# 05_MIMXRT1170_PART1.net
KiCad netlist of a schematic drawn in Altium Designer
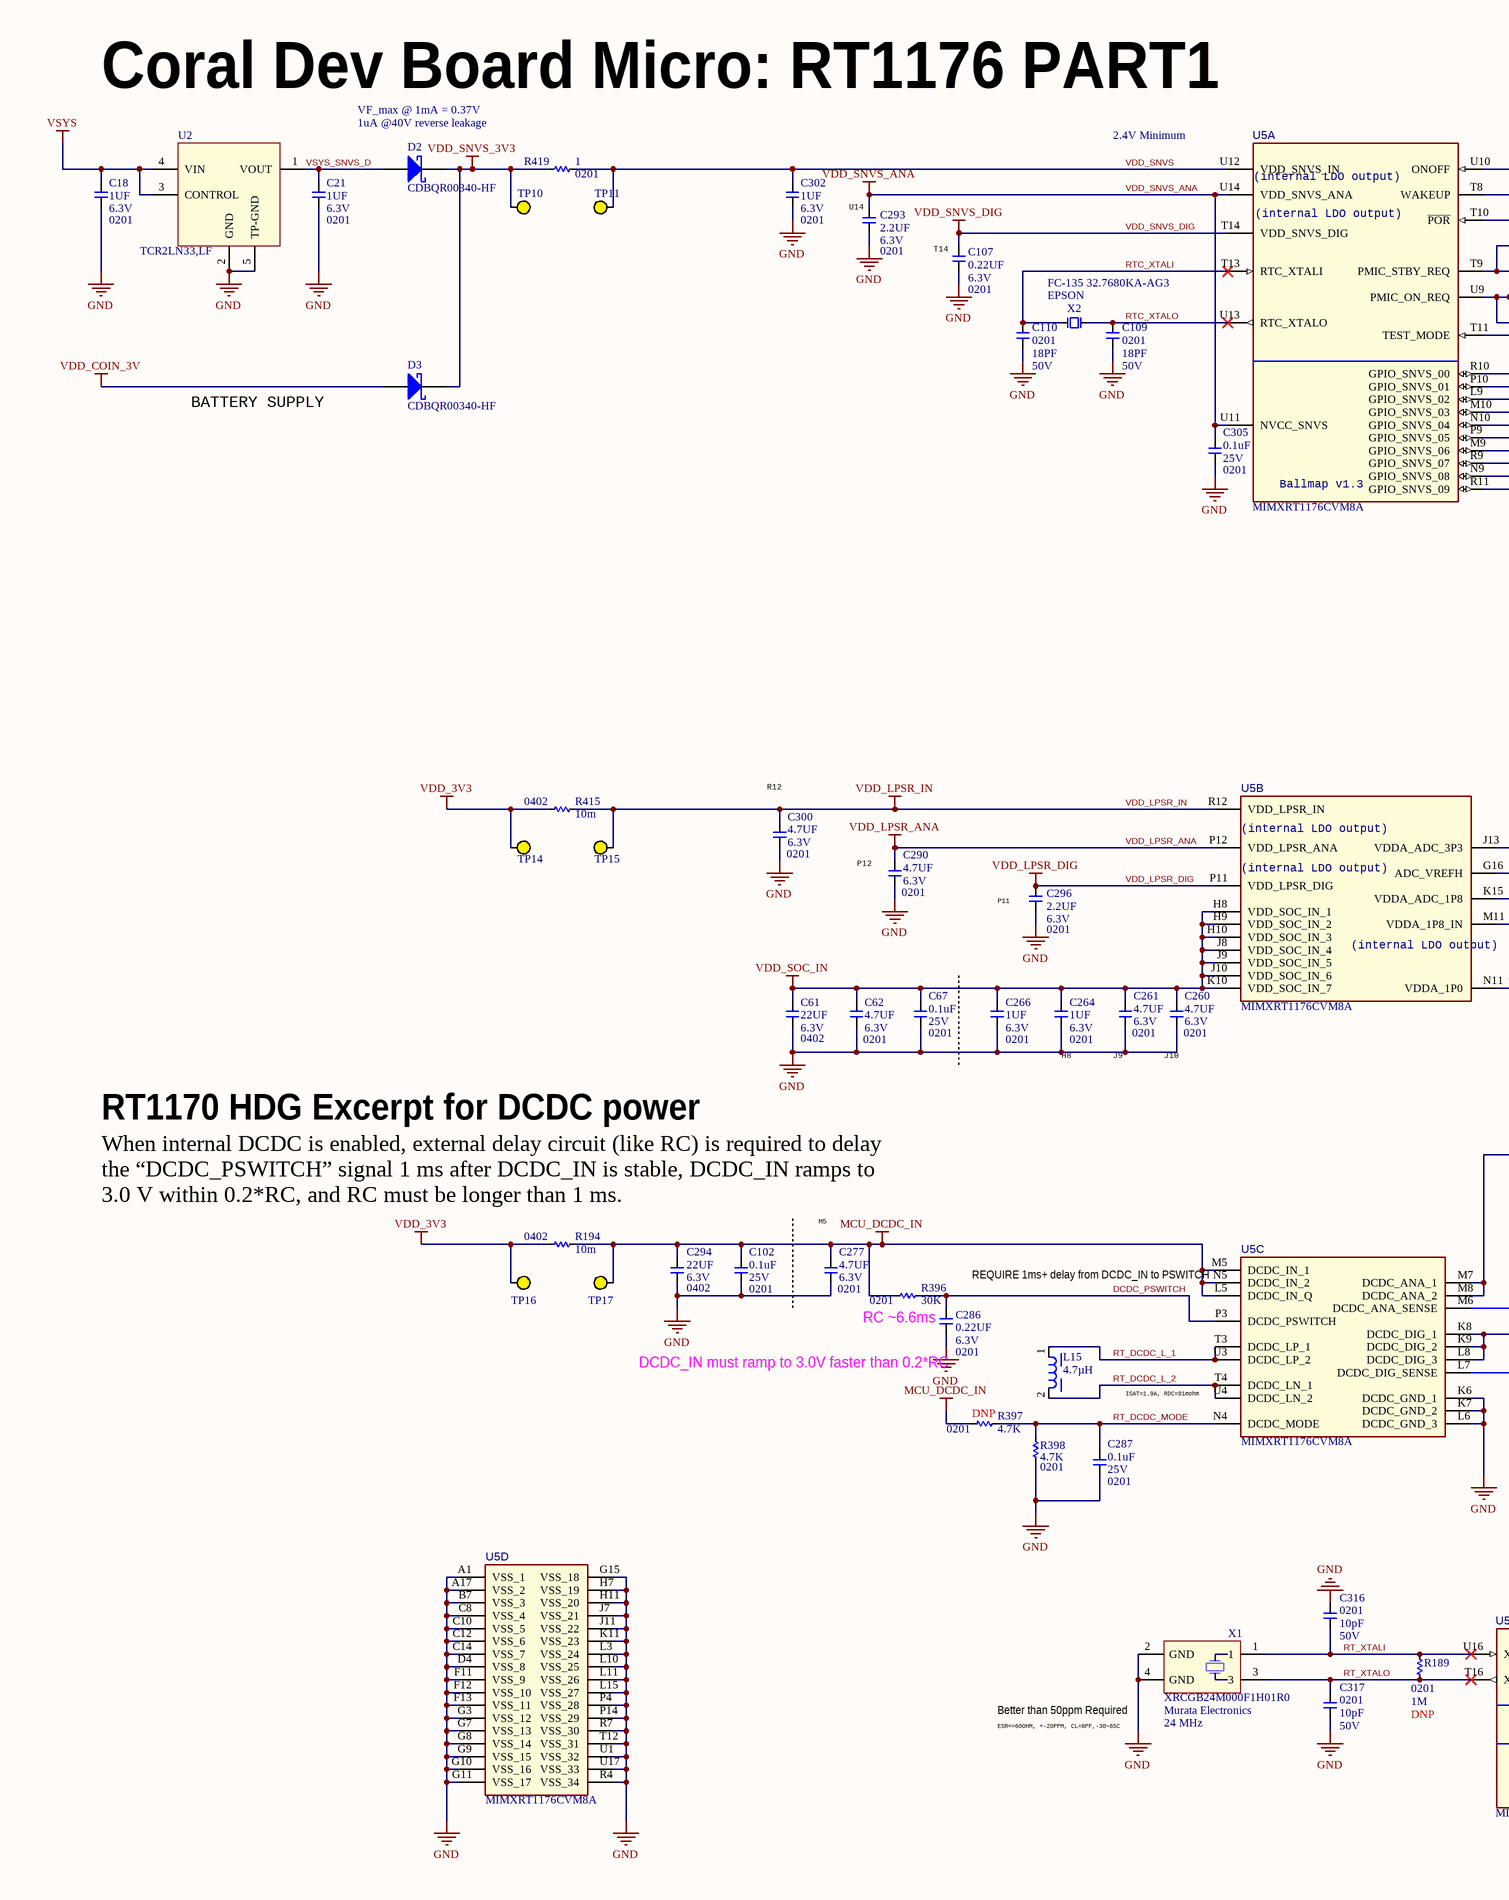
[diagram p0: 05 MIMXRT1170 PART1.SchDoc, left]
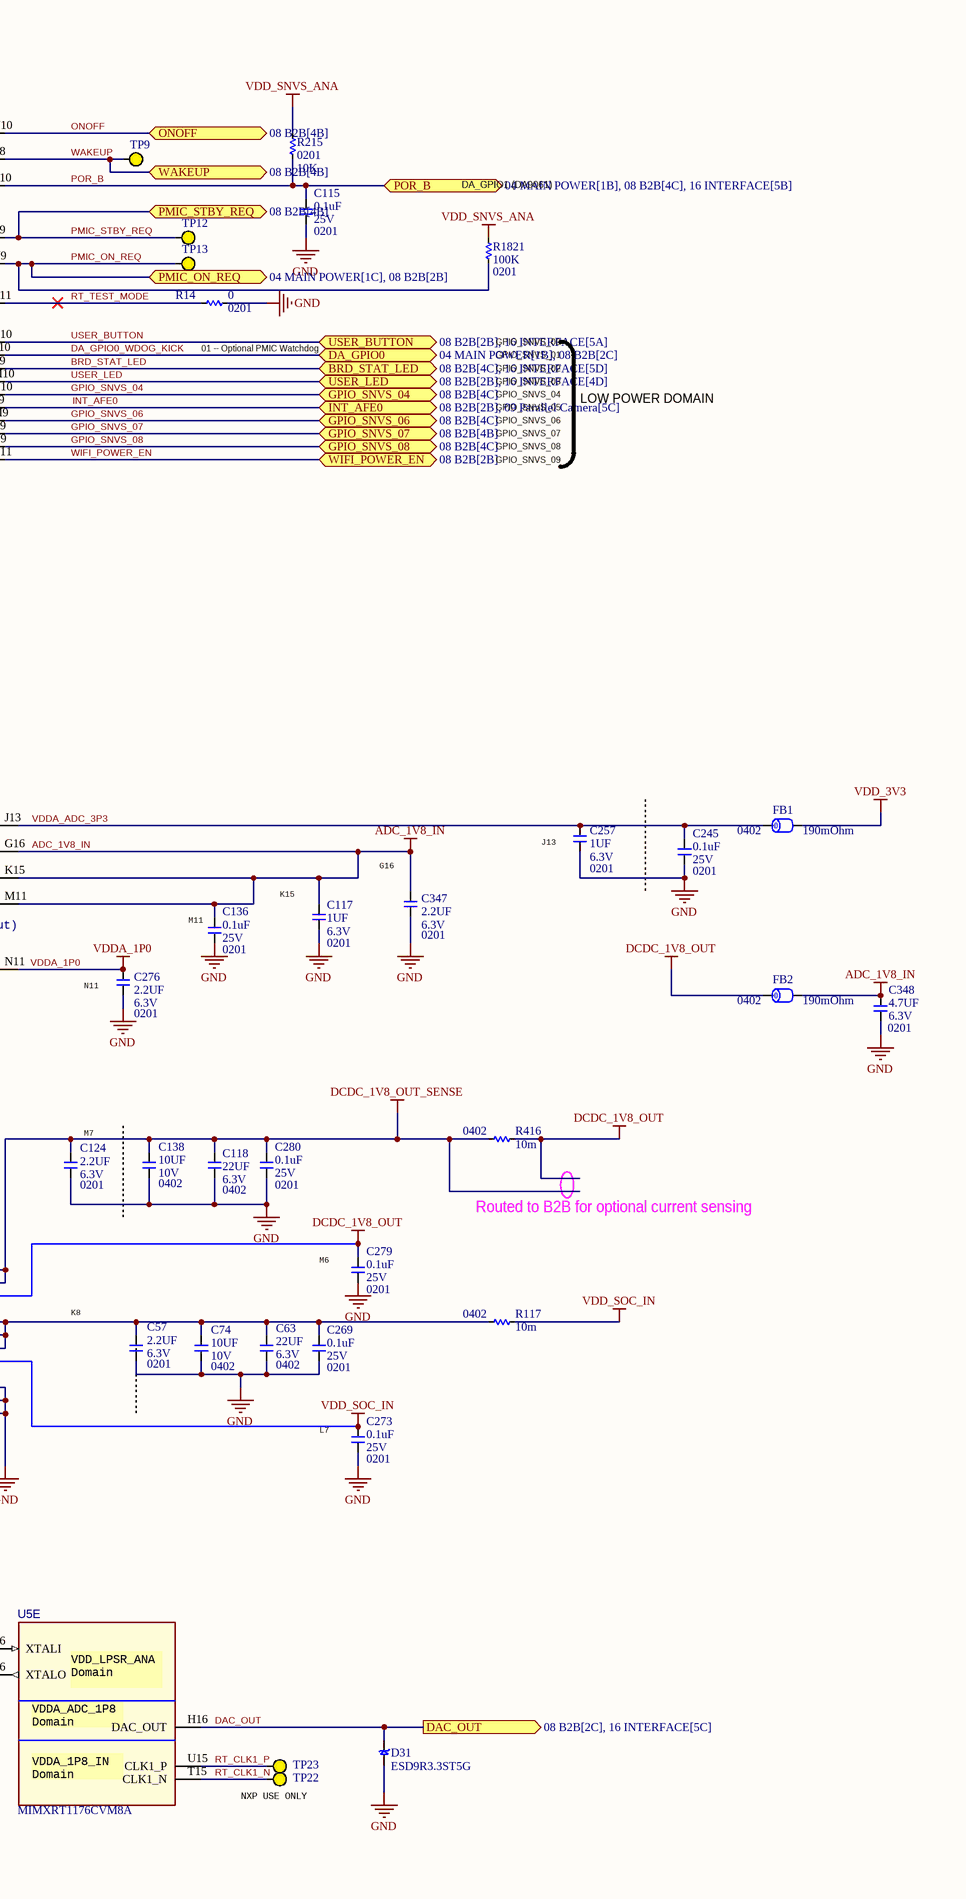
[diagram p1: 05 MIMXRT1170 PART1.SchDoc, right]

(export (version "E")
  (design (tool "Eeschema 10.0.6"))
  (components
    (comp (ref "C18")
      (value "1UF")
      (footprint "C0201_H0.39MM")
      (description "CAP, CER, X6S, 1uF, 20%, 6.3V, 0201, 0.39mm")
      (fields
        (field (name "MFG") "MURATA")
        (field (name "PACKAGE") "0201")
        (field (name "VOLTAGE") "6.3V")
        (field (name "TOLERANCE") "20%")
      )
      (libsource (lib "AltiumReleaseLibDB") (part "__Template_Cap"))
    )
    (comp (ref "C21")
      (value "1UF")
      (footprint "C0201_H0.39MM")
      (description "CAP, CER, X6S, 1uF, 20%, 6.3V, 0201, 0.39mm")
      (fields
        (field (name "MFG") "MURATA")
        (field (name "PACKAGE") "0201")
        (field (name "VOLTAGE") "6.3V")
        (field (name "TOLERANCE") "20%")
      )
      (libsource (lib "AltiumReleaseLibDB") (part "__Template_Cap"))
    )
    (comp (ref "C57")
      (value "2.2UF")
      (footprint "C0201_H0.39MM")
      (description "CAP, CER, X5R, 2.2uF, 20%, 6.3V, 0201, 0.39mm")
      (fields
        (field (name "MFG") "YAGEO")
        (field (name "PACKAGE") "0201")
        (field (name "VOLTAGE") "6.3V")
        (field (name "TOLERANCE") "20%")
      )
      (libsource (lib "AltiumReleaseLibDB") (part "__Template_Cap"))
    )
    (comp (ref "C61")
      (value "22UF")
      (footprint "C0402")
      (description "CAP, CER, X5R, 22uF, 20%, 6.3V, 0402")
      (fields
        (field (name "MFG") "AVX")
        (field (name "PACKAGE") "0402")
        (field (name "VOLTAGE") "6.3V")
        (field (name "TOLERANCE") "20%")
      )
      (libsource (lib "AltiumReleaseLibDB") (part "__Template_Cap"))
    )
    (comp (ref "C62")
      (value "4.7UF")
      (footprint "C0201Y")
      (description "CAP, CER, X5R, 4.7uF, 20%, 6.3V, 0201")
      (fields
        (field (name "MFG") "MURATA")
        (field (name "PACKAGE") "0201")
        (field (name "VOLTAGE") "6.3V")
        (field (name "TOLERANCE") "20%")
      )
      (libsource (lib "AltiumReleaseLibDB") (part "__Template_Cap"))
    )
    (comp (ref "C63")
      (value "22UF")
      (footprint "C0402")
      (description "CAP, CER, X5R, 22uF, 20%, 6.3V, 0402")
      (fields
        (field (name "MFG") "AVX")
        (field (name "PACKAGE") "0402")
        (field (name "VOLTAGE") "6.3V")
        (field (name "TOLERANCE") "20%")
      )
      (libsource (lib "AltiumReleaseLibDB") (part "__Template_Cap"))
    )
    (comp (ref "C67")
      (value "0.1uF")
      (footprint "C0201Y")
      (description "CAP, CER, X5R, 0.1uF, 25V, 20%, 0201, 0.33mm T")
      (fields
        (field (name "MFG") "MURATA")
        (field (name "PACKAGE") "0201")
        (field (name "VOLTAGE") "25V")
        (field (name "TOLERANCE") "20%")
      )
      (libsource (lib "AltiumReleaseLibDB") (part "__Template_Cap"))
    )
    (comp (ref "C74")
      (value "10UF")
      (footprint "C0402")
      (description "CAP, CER, X5R, 10uF, 10V, 20%, 0402, 0.7mm T")
      (fields
        (field (name "MFG") "SAMSUNG")
        (field (name "PACKAGE") "0402")
        (field (name "VOLTAGE") "10V")
        (field (name "TOLERANCE") "20%")
      )
      (libsource (lib "AltiumReleaseLibDB") (part "__Template_Cap"))
    )
    (comp (ref "C102")
      (value "0.1uF")
      (footprint "C0201Y")
      (description "CAP, CER, X5R, 0.1uF, 25V, 20%, 0201, 0.33mm T")
      (fields
        (field (name "MFG") "MURATA")
        (field (name "PACKAGE") "0201")
        (field (name "VOLTAGE") "25V")
        (field (name "TOLERANCE") "20%")
      )
      (libsource (lib "AltiumReleaseLibDB") (part "__Template_Cap"))
    )
    (comp (ref "C107")
      (value "0.22UF")
      (footprint "C0201")
      (description "CAP, CER, X5R, 0.22uF, 6.3V, 10%, 0201, 0.33mm T")
      (fields
        (field (name "MFG") "TDK")
        (field (name "PACKAGE") "0201")
        (field (name "VOLTAGE") "6.3V")
        (field (name "TOLERANCE") "10%")
      )
      (libsource (lib "AltiumReleaseLibDB") (part "__Template_Cap"))
    )
    (comp (ref "C109")
      (value "18PF")
      (footprint "C0201Y")
      (description "CAP, CER, C0G, 18pF, 50V, 2%, 0201, 0.33mm T")
      (fields
        (field (name "MFG") "MURATA")
        (field (name "PACKAGE") "0201")
        (field (name "VOLTAGE") "50V")
        (field (name "TOLERANCE") "2%")
      )
      (libsource (lib "AltiumReleaseLibDB") (part "__Template_Cap"))
    )
    (comp (ref "C110")
      (value "18PF")
      (footprint "C0201Y")
      (description "CAP, CER, C0G, 18pF, 50V, 2%, 0201, 0.33mm T")
      (fields
        (field (name "MFG") "MURATA")
        (field (name "PACKAGE") "0201")
        (field (name "VOLTAGE") "50V")
        (field (name "TOLERANCE") "2%")
      )
      (libsource (lib "AltiumReleaseLibDB") (part "__Template_Cap"))
    )
    (comp (ref "C115")
      (value "0.1uF")
      (footprint "C0201Y")
      (description "CAP, CER, X5R, 0.1uF, 25V, 20%, 0201, 0.33mm T")
      (fields
        (field (name "MFG") "MURATA")
        (field (name "PACKAGE") "0201")
        (field (name "VOLTAGE") "25V")
        (field (name "TOLERANCE") "20%")
      )
      (libsource (lib "AltiumReleaseLibDB") (part "__Template_Cap"))
    )
    (comp (ref "C117")
      (value "1UF")
      (footprint "C0201_H0.39MM")
      (description "CAP, CER, X6S, 1uF, 20%, 6.3V, 0201, 0.39mm")
      (fields
        (field (name "MFG") "MURATA")
        (field (name "PACKAGE") "0201")
        (field (name "VOLTAGE") "6.3V")
        (field (name "TOLERANCE") "20%")
      )
      (libsource (lib "AltiumReleaseLibDB") (part "__Template_Cap"))
    )
    (comp (ref "C118")
      (value "22UF")
      (footprint "C0402")
      (description "CAP, CER, X5R, 22uF, 20%, 6.3V, 0402")
      (fields
        (field (name "MFG") "AVX")
        (field (name "PACKAGE") "0402")
        (field (name "VOLTAGE") "6.3V")
        (field (name "TOLERANCE") "20%")
      )
      (libsource (lib "AltiumReleaseLibDB") (part "__Template_Cap"))
    )
    (comp (ref "C124")
      (value "2.2UF")
      (footprint "C0201_H0.39MM")
      (description "CAP, CER, X5R, 2.2uF, 20%, 6.3V, 0201, 0.39mm")
      (fields
        (field (name "MFG") "YAGEO")
        (field (name "PACKAGE") "0201")
        (field (name "VOLTAGE") "6.3V")
        (field (name "TOLERANCE") "20%")
      )
      (libsource (lib "AltiumReleaseLibDB") (part "__Template_Cap"))
    )
    (comp (ref "C136")
      (value "0.1uF")
      (footprint "C0201Y")
      (description "CAP, CER, X5R, 0.1uF, 25V, 20%, 0201, 0.33mm T")
      (fields
        (field (name "MFG") "MURATA")
        (field (name "PACKAGE") "0201")
        (field (name "VOLTAGE") "25V")
        (field (name "TOLERANCE") "20%")
      )
      (libsource (lib "AltiumReleaseLibDB") (part "__Template_Cap"))
    )
    (comp (ref "C138")
      (value "10UF")
      (footprint "C0402")
      (description "CAP, CER, X5R, 10uF, 10V, 20%, 0402, 0.7mm T")
      (fields
        (field (name "MFG") "SAMSUNG")
        (field (name "PACKAGE") "0402")
        (field (name "VOLTAGE") "10V")
        (field (name "TOLERANCE") "20%")
      )
      (libsource (lib "AltiumReleaseLibDB") (part "__Template_Cap"))
    )
    (comp (ref "C245")
      (value "0.1uF")
      (footprint "C0201Y")
      (description "CAP, CER, X5R, 0.1uF, 25V, 20%, 0201, 0.33mm T")
      (fields
        (field (name "MFG") "MURATA")
        (field (name "PACKAGE") "0201")
        (field (name "VOLTAGE") "25V")
        (field (name "TOLERANCE") "20%")
      )
      (libsource (lib "AltiumReleaseLibDB") (part "__Template_Cap"))
    )
    (comp (ref "C257")
      (value "1UF")
      (footprint "C0201_H0.39MM")
      (description "CAP, CER, X6S, 1uF, 20%, 6.3V, 0201, 0.39mm")
      (fields
        (field (name "MFG") "MURATA")
        (field (name "PACKAGE") "0201")
        (field (name "VOLTAGE") "6.3V")
        (field (name "TOLERANCE") "20%")
      )
      (libsource (lib "AltiumReleaseLibDB") (part "__Template_Cap"))
    )
    (comp (ref "C260")
      (value "4.7UF")
      (footprint "C0201Y")
      (description "CAP, CER, X5R, 4.7uF, 20%, 6.3V, 0201")
      (fields
        (field (name "MFG") "MURATA")
        (field (name "PACKAGE") "0201")
        (field (name "VOLTAGE") "6.3V")
        (field (name "TOLERANCE") "20%")
      )
      (libsource (lib "AltiumReleaseLibDB") (part "__Template_Cap"))
    )
    (comp (ref "C261")
      (value "4.7UF")
      (footprint "C0201Y")
      (description "CAP, CER, X5R, 4.7uF, 20%, 6.3V, 0201")
      (fields
        (field (name "MFG") "MURATA")
        (field (name "PACKAGE") "0201")
        (field (name "VOLTAGE") "6.3V")
        (field (name "TOLERANCE") "20%")
      )
      (libsource (lib "AltiumReleaseLibDB") (part "__Template_Cap"))
    )
    (comp (ref "C264")
      (value "1UF")
      (footprint "C0201_H0.39MM")
      (description "CAP, CER, X6S, 1uF, 20%, 6.3V, 0201, 0.39mm")
      (fields
        (field (name "MFG") "MURATA")
        (field (name "PACKAGE") "0201")
        (field (name "VOLTAGE") "6.3V")
        (field (name "TOLERANCE") "20%")
      )
      (libsource (lib "AltiumReleaseLibDB") (part "__Template_Cap"))
    )
    (comp (ref "C266")
      (value "1UF")
      (footprint "C0201_H0.39MM")
      (description "CAP, CER, X6S, 1uF, 20%, 6.3V, 0201, 0.39mm")
      (fields
        (field (name "MFG") "MURATA")
        (field (name "PACKAGE") "0201")
        (field (name "VOLTAGE") "6.3V")
        (field (name "TOLERANCE") "20%")
      )
      (libsource (lib "AltiumReleaseLibDB") (part "__Template_Cap"))
    )
    (comp (ref "C269")
      (value "0.1uF")
      (footprint "C0201Y")
      (description "CAP, CER, X5R, 0.1uF, 25V, 20%, 0201, 0.33mm T")
      (fields
        (field (name "MFG") "MURATA")
        (field (name "PACKAGE") "0201")
        (field (name "VOLTAGE") "25V")
        (field (name "TOLERANCE") "20%")
      )
      (libsource (lib "AltiumReleaseLibDB") (part "__Template_Cap"))
    )
    (comp (ref "C273")
      (value "0.1uF")
      (footprint "C0201Y")
      (description "CAP, CER, X5R, 0.1uF, 25V, 20%, 0201, 0.33mm T")
      (fields
        (field (name "MFG") "MURATA")
        (field (name "PACKAGE") "0201")
        (field (name "VOLTAGE") "25V")
        (field (name "TOLERANCE") "20%")
      )
      (libsource (lib "AltiumReleaseLibDB") (part "__Template_Cap"))
    )
    (comp (ref "C276")
      (value "2.2UF")
      (footprint "C0201_H0.39MM")
      (description "CAP, CER, X5R, 2.2uF, 20%, 6.3V, 0201, 0.39mm")
      (fields
        (field (name "MFG") "YAGEO")
        (field (name "PACKAGE") "0201")
        (field (name "VOLTAGE") "6.3V")
        (field (name "TOLERANCE") "20%")
      )
      (libsource (lib "AltiumReleaseLibDB") (part "__Template_Cap"))
    )
    (comp (ref "C277")
      (value "4.7UF")
      (footprint "C0201Y")
      (description "CAP, CER, X5R, 4.7uF, 20%, 6.3V, 0201")
      (fields
        (field (name "MFG") "MURATA")
        (field (name "PACKAGE") "0201")
        (field (name "VOLTAGE") "6.3V")
        (field (name "TOLERANCE") "20%")
      )
      (libsource (lib "AltiumReleaseLibDB") (part "__Template_Cap"))
    )
    (comp (ref "C279")
      (value "0.1uF")
      (footprint "C0201Y")
      (description "CAP, CER, X5R, 0.1uF, 25V, 20%, 0201, 0.33mm T")
      (fields
        (field (name "MFG") "MURATA")
        (field (name "PACKAGE") "0201")
        (field (name "VOLTAGE") "25V")
        (field (name "TOLERANCE") "20%")
      )
      (libsource (lib "AltiumReleaseLibDB") (part "__Template_Cap"))
    )
    (comp (ref "C280")
      (value "0.1uF")
      (footprint "C0201Y")
      (description "CAP, CER, X5R, 0.1uF, 25V, 20%, 0201, 0.33mm T")
      (fields
        (field (name "MFG") "MURATA")
        (field (name "PACKAGE") "0201")
        (field (name "VOLTAGE") "25V")
        (field (name "TOLERANCE") "20%")
      )
      (libsource (lib "AltiumReleaseLibDB") (part "__Template_Cap"))
    )
    (comp (ref "C286")
      (value "0.22UF")
      (footprint "C0201")
      (description "CAP, CER, X5R, 0.22uF, 6.3V, 10%, 0201, 0.33mm T")
      (fields
        (field (name "MFG") "TDK")
        (field (name "PACKAGE") "0201")
        (field (name "VOLTAGE") "6.3V")
        (field (name "TOLERANCE") "10%")
      )
      (libsource (lib "AltiumReleaseLibDB") (part "__Template_Cap"))
    )
    (comp (ref "C287")
      (value "0.1uF")
      (footprint "C0201Y")
      (description "CAP, CER, X5R, 0.1uF, 25V, 20%, 0201, 0.33mm T")
      (fields
        (field (name "MFG") "MURATA")
        (field (name "PACKAGE") "0201")
        (field (name "VOLTAGE") "25V")
        (field (name "TOLERANCE") "20%")
      )
      (libsource (lib "AltiumReleaseLibDB") (part "__Template_Cap"))
    )
    (comp (ref "C290")
      (value "4.7UF")
      (footprint "C0201Y")
      (description "CAP, CER, X5R, 4.7uF, 20%, 6.3V, 0201")
      (fields
        (field (name "MFG") "MURATA")
        (field (name "PACKAGE") "0201")
        (field (name "VOLTAGE") "6.3V")
        (field (name "TOLERANCE") "20%")
      )
      (libsource (lib "AltiumReleaseLibDB") (part "__Template_Cap"))
    )
    (comp (ref "C293")
      (value "2.2UF")
      (footprint "C0201_H0.39MM")
      (description "CAP, CER, X5R, 2.2uF, 20%, 6.3V, 0201, 0.39mm")
      (fields
        (field (name "MFG") "YAGEO")
        (field (name "PACKAGE") "0201")
        (field (name "VOLTAGE") "6.3V")
        (field (name "TOLERANCE") "20%")
      )
      (libsource (lib "AltiumReleaseLibDB") (part "__Template_Cap"))
    )
    (comp (ref "C294")
      (value "22UF")
      (footprint "C0402")
      (description "CAP, CER, X5R, 22uF, 20%, 6.3V, 0402")
      (fields
        (field (name "MFG") "AVX")
        (field (name "PACKAGE") "0402")
        (field (name "VOLTAGE") "6.3V")
        (field (name "TOLERANCE") "20%")
      )
      (libsource (lib "AltiumReleaseLibDB") (part "__Template_Cap"))
    )
    (comp (ref "C296")
      (value "2.2UF")
      (footprint "C0201_H0.39MM")
      (description "CAP, CER, X5R, 2.2uF, 20%, 6.3V, 0201, 0.39mm")
      (fields
        (field (name "MFG") "YAGEO")
        (field (name "PACKAGE") "0201")
        (field (name "VOLTAGE") "6.3V")
        (field (name "TOLERANCE") "20%")
      )
      (libsource (lib "AltiumReleaseLibDB") (part "__Template_Cap"))
    )
    (comp (ref "C300")
      (value "4.7UF")
      (footprint "C0201Y")
      (description "CAP, CER, X5R, 4.7uF, 20%, 6.3V, 0201")
      (fields
        (field (name "MFG") "MURATA")
        (field (name "PACKAGE") "0201")
        (field (name "VOLTAGE") "6.3V")
        (field (name "TOLERANCE") "20%")
      )
      (libsource (lib "AltiumReleaseLibDB") (part "__Template_Cap"))
    )
    (comp (ref "C302")
      (value "1UF")
      (footprint "C0201_H0.39MM")
      (description "CAP, CER, X6S, 1uF, 20%, 6.3V, 0201, 0.39mm")
      (fields
        (field (name "MFG") "MURATA")
        (field (name "PACKAGE") "0201")
        (field (name "VOLTAGE") "6.3V")
        (field (name "TOLERANCE") "20%")
      )
      (libsource (lib "AltiumReleaseLibDB") (part "__Template_Cap"))
    )
    (comp (ref "C305")
      (value "0.1uF")
      (footprint "C0201Y")
      (description "CAP, CER, X5R, 0.1uF, 25V, 20%, 0201, 0.33mm T")
      (fields
        (field (name "MFG") "MURATA")
        (field (name "PACKAGE") "0201")
        (field (name "VOLTAGE") "25V")
        (field (name "TOLERANCE") "20%")
      )
      (libsource (lib "AltiumReleaseLibDB") (part "__Template_Cap"))
    )
    (comp (ref "C316")
      (value "10pF")
      (footprint "C0201Y")
      (description "CAP, CER, NP0, 10pf, 50V, 5%, 0201, 0.33mm T")
      (fields
        (field (name "MFG") "MURATA")
        (field (name "PACKAGE") "0201")
        (field (name "VOLTAGE") "50V")
        (field (name "TOLERANCE") "5%")
      )
      (libsource (lib "AltiumReleaseLibDB") (part "__Template_Cap"))
    )
    (comp (ref "C317")
      (value "10pF")
      (footprint "C0201Y")
      (description "CAP, CER, NP0, 10pf, 50V, 5%, 0201, 0.33mm T")
      (fields
        (field (name "MFG") "MURATA")
        (field (name "PACKAGE") "0201")
        (field (name "VOLTAGE") "50V")
        (field (name "TOLERANCE") "5%")
      )
      (libsource (lib "AltiumReleaseLibDB") (part "__Template_Cap"))
    )
    (comp (ref "C347")
      (value "2.2UF")
      (footprint "C0201_H0.39MM")
      (description "CAP, CER, X5R, 2.2uF, 20%, 6.3V, 0201, 0.39mm")
      (fields
        (field (name "MFG") "YAGEO")
        (field (name "PACKAGE") "0201")
        (field (name "VOLTAGE") "6.3V")
        (field (name "TOLERANCE") "20%")
      )
      (libsource (lib "AltiumReleaseLibDB") (part "__Template_Cap"))
    )
    (comp (ref "C348")
      (value "4.7UF")
      (footprint "C0201Y")
      (description "CAP, CER, X5R, 4.7uF, 20%, 6.3V, 0201")
      (fields
        (field (name "MFG") "MURATA")
        (field (name "PACKAGE") "0201")
        (field (name "VOLTAGE") "6.3V")
        (field (name "TOLERANCE") "20%")
      )
      (libsource (lib "AltiumReleaseLibDB") (part "__Template_Cap"))
    )
    (comp (ref "D2")
      (value "CDBQR00340-HF")
      (footprint "D0402_H0.55MM")
      (description "DIODE, SCHOTTKY, 40V VRRM, 30mA IO, 500mA SURGE, 0402")
      (fields (field (name "MFG") "Comchip Technology") (field (name "Comment") "__Template_DIODE_SCHOTTKY"))
      (libsource (lib "AltiumReleaseLibDB") (part "__Template_DIODE_SCHOTTKY"))
    )
    (comp (ref "D3")
      (value "CDBQR00340-HF")
      (footprint "D0402_H0.55MM")
      (description "DIODE, SCHOTTKY, 40V VRRM, 30mA IO, 500mA SURGE, 0402")
      (fields (field (name "MFG") "Comchip Technology") (field (name "Comment") "__Template_DIODE_SCHOTTKY"))
      (libsource (lib "AltiumReleaseLibDB") (part "__Template_DIODE_SCHOTTKY"))
    )
    (comp (ref "D31")
      (value "ESD9R3.3ST5G")
      (footprint "SOD1060X40")
      (description "TVS, DIODE, UNIDIR, 3.3VRWM, 4.8VBR, 7.8VCL, SOD-923")
      (fields (field (name "MFG") "ON Semiconductor") (field (name "Comment") "__Template_Diode_TVS_A/K"))
      (libsource (lib "AltiumReleaseLibDB") (part "__Template_Diode_TVS_A/K"))
    )
    (comp (ref "FB1")
      (value "__Template_Ferrite_Bead")
      (footprint "L0402_H0.55MM")
      (description "FERRITE, BEAD, 120 OHMS@100MHZ, 25%, 550mA, 190 mOHM DCR, 0402")
      (fields
        (field (name "MFG") "Murata Electronics")
        (field (name "PACKAGE") "0402")
        (field (name "RDC MAX") "190mOhm")
      )
      (libsource (lib "AltiumReleaseLibDB") (part "__Template_Ferrite_Bead"))
    )
    (comp (ref "FB2")
      (value "__Template_Ferrite_Bead")
      (footprint "L0402_H0.55MM")
      (description "FERRITE, BEAD, 120 OHMS@100MHZ, 25%, 550mA, 190 mOHM DCR, 0402")
      (fields
        (field (name "MFG") "Murata Electronics")
        (field (name "PACKAGE") "0402")
        (field (name "RDC MAX") "190mOhm")
      )
      (libsource (lib "AltiumReleaseLibDB") (part "__Template_Ferrite_Bead"))
    )
    (comp (ref "L15")
      (value "4.7µH")
      (footprint "IND_74404041047")
      (description "IND, WIREWOUND, SEMI-SHIELDED, 4.7uH, 1.55A, 20%, DCR 0.091, SMD")
      (fields (field (name "MFG") "Würth Elektronik") (field (name "TOLERANCE") "20%"))
      (libsource (lib "AltiumReleaseLibDB") (part "IND_74404041047"))
    )
    (comp (ref "R14")
      (value "0")
      (footprint "R0201")
      (description "RES, 0.0, 1/20W, 0201")
      (fields (field (name "MFG") "PANASONIC") (field (name "PACKAGE") "0201") (field (name "POWER") "1/20W"))
      (libsource (lib "AltiumReleaseLibDB") (part "__Template_Resistor"))
    )
    (comp (ref "R117")
      (value "10m")
      (footprint "R0402")
      (description "RES, 0.01, 5%, 1/4W, 0402")
      (fields (field (name "MFG") "YAGEO") (field (name "PACKAGE") "0402") (field (name "POWER") "1/4W"))
      (libsource (lib "AltiumReleaseLibDB") (part "__Template_Resistor"))
    )
    (comp (ref "R189")
      (value "1M")
      (footprint "R0201")
      (description "RES, 1M, 1%, 1/20W, 0201")
      (fields
        (field (name "MFG") "PANASONIC")
        (field (name "PACKAGE") "0201")
        (field (name "POWER") "1/20W")
        (field (name "DNP") "DNP")
      )
      (libsource (lib "AltiumReleaseLibDB") (part "__Template_Resistor"))
    )
    (comp (ref "R194")
      (value "10m")
      (footprint "R0402")
      (description "RES, 0.01, 5%, 1/4W, 0402")
      (fields (field (name "MFG") "YAGEO") (field (name "PACKAGE") "0402") (field (name "POWER") "1/4W"))
      (libsource (lib "AltiumReleaseLibDB") (part "__Template_Resistor"))
    )
    (comp (ref "R215")
      (value "10K")
      (footprint "R0201")
      (description "RES, 10K, 1%, 1/20W, 0201")
      (fields (field (name "MFG") "YAGEO") (field (name "PACKAGE") "0201") (field (name "POWER") "1/20W"))
      (libsource (lib "AltiumReleaseLibDB") (part "__Template_Resistor"))
    )
    (comp (ref "R396")
      (value "30K")
      (footprint "R0201")
      (description "RES, 30K, 5%, 1/20W, 0201")
      (fields (field (name "MFG") "PANASONIC") (field (name "PACKAGE") "0201") (field (name "POWER") "1/20W"))
      (libsource (lib "AltiumReleaseLibDB") (part "__Template_Resistor"))
    )
    (comp (ref "R397")
      (value "4.7K")
      (footprint "R0201")
      (description "RES, 4.7K, 5%, 1/20W, 0201")
      (fields
        (field (name "MFG") "YAGEO")
        (field (name "PACKAGE") "0201")
        (field (name "POWER") "1/20W")
        (field (name "DNP") "DNP")
      )
      (libsource (lib "AltiumReleaseLibDB") (part "__Template_Resistor"))
    )
    (comp (ref "R398")
      (value "4.7K")
      (footprint "R0201")
      (description "RES, 4.7K, 5%, 1/20W, 0201")
      (fields (field (name "MFG") "YAGEO") (field (name "PACKAGE") "0201") (field (name "POWER") "1/20W"))
      (libsource (lib "AltiumReleaseLibDB") (part "__Template_Resistor"))
    )
    (comp (ref "R415")
      (value "10m")
      (footprint "R0402")
      (description "RES, 0.01, 5%, 1/4W, 0402")
      (fields (field (name "MFG") "YAGEO") (field (name "PACKAGE") "0402") (field (name "POWER") "1/4W"))
      (libsource (lib "AltiumReleaseLibDB") (part "__Template_Resistor"))
    )
    (comp (ref "R416")
      (value "10m")
      (footprint "R0402")
      (description "RES, 0.01, 5%, 1/4W, 0402")
      (fields (field (name "MFG") "YAGEO") (field (name "PACKAGE") "0402") (field (name "POWER") "1/4W"))
      (libsource (lib "AltiumReleaseLibDB") (part "__Template_Resistor"))
    )
    (comp (ref "R419")
      (value "1")
      (footprint "R0201")
      (description "RES, 1.0, 1%, 1/20W, 0201")
      (fields
        (field (name "MFG") "STACKPOLE ELECTRONICS")
        (field (name "PACKAGE") "0201")
        (field (name "POWER") "1/20W")
      )
      (libsource (lib "AltiumReleaseLibDB") (part "__Template_Resistor"))
    )
    (comp (ref "R1821")
      (value "100K")
      (footprint "R0201")
      (description "RES, 100K, 1%, 1/20W, 0201")
      (fields (field (name "MFG") "PANASONIC") (field (name "PACKAGE") "0201") (field (name "POWER") "1/20W"))
      (libsource (lib "AltiumReleaseLibDB") (part "__Template_Resistor"))
    )
    (comp (ref "TP9")
      (value "TESTPAD_30MIL")
      (footprint "TESTPAD_SMT_30MIL")
      (description "TESTPAD_SMT_30MIL")
      (fields (field (name "MFG") "_PCB Feature"))
      (libsource (lib "AltiumReleaseLibDB") (part "TESTPAD_30MIL"))
    )
    (comp (ref "TP10")
      (value "TESTPAD_30MIL")
      (footprint "TESTPAD_SMT_30MIL")
      (description "TESTPAD_SMT_30MIL")
      (fields (field (name "MFG") "_PCB Feature"))
      (libsource (lib "AltiumReleaseLibDB") (part "TESTPAD_30MIL"))
    )
    (comp (ref "TP11")
      (value "TESTPAD_30MIL")
      (footprint "TESTPAD_SMT_30MIL")
      (description "TESTPAD_SMT_30MIL")
      (fields (field (name "MFG") "_PCB Feature"))
      (libsource (lib "AltiumReleaseLibDB") (part "TESTPAD_30MIL"))
    )
    (comp (ref "TP12")
      (value "TESTPAD_30MIL")
      (footprint "TESTPAD_SMT_30MIL")
      (description "TESTPAD_SMT_30MIL")
      (fields (field (name "MFG") "_PCB Feature"))
      (libsource (lib "AltiumReleaseLibDB") (part "TESTPAD_30MIL"))
    )
    (comp (ref "TP13")
      (value "TESTPAD_30MIL")
      (footprint "TESTPAD_SMT_30MIL")
      (description "TESTPAD_SMT_30MIL")
      (fields (field (name "MFG") "_PCB Feature"))
      (libsource (lib "AltiumReleaseLibDB") (part "TESTPAD_30MIL"))
    )
    (comp (ref "TP14")
      (value "TESTPAD_30MIL")
      (footprint "TESTPAD_SMT_30MIL")
      (description "TESTPAD_SMT_30MIL")
      (fields (field (name "MFG") "_PCB Feature"))
      (libsource (lib "AltiumReleaseLibDB") (part "TESTPAD_30MIL"))
    )
    (comp (ref "TP15")
      (value "TESTPAD_30MIL")
      (footprint "TESTPAD_SMT_30MIL")
      (description "TESTPAD_SMT_30MIL")
      (fields (field (name "MFG") "_PCB Feature"))
      (libsource (lib "AltiumReleaseLibDB") (part "TESTPAD_30MIL"))
    )
    (comp (ref "TP16")
      (value "TESTPAD_30MIL")
      (footprint "TESTPAD_SMT_30MIL")
      (description "TESTPAD_SMT_30MIL")
      (fields (field (name "MFG") "_PCB Feature"))
      (libsource (lib "AltiumReleaseLibDB") (part "TESTPAD_30MIL"))
    )
    (comp (ref "TP17")
      (value "TESTPAD_30MIL")
      (footprint "TESTPAD_SMT_30MIL")
      (description "TESTPAD_SMT_30MIL")
      (fields (field (name "MFG") "_PCB Feature"))
      (libsource (lib "AltiumReleaseLibDB") (part "TESTPAD_30MIL"))
    )
    (comp (ref "TP22")
      (value "TESTPAD_30MIL")
      (footprint "TESTPAD_SMT_30MIL")
      (description "TESTPAD_SMT_30MIL")
      (fields (field (name "MFG") "_PCB Feature"))
      (libsource (lib "AltiumReleaseLibDB") (part "TESTPAD_30MIL"))
    )
    (comp (ref "TP23")
      (value "TESTPAD_30MIL")
      (footprint "TESTPAD_SMT_30MIL")
      (description "TESTPAD_SMT_30MIL")
      (fields (field (name "MFG") "_PCB Feature"))
      (libsource (lib "AltiumReleaseLibDB") (part "TESTPAD_30MIL"))
    )
    (comp (ref "U2")
      (value "REG_LIN_TCR2LN33")
      (footprint "SDFN80X80X40-5")
      (description "IC, REG, TCR2LN33, LINEAR, LDO, 5.5V VIN, 3.3V VOUT, CMOS O/P, SDFN-4")
      (fields (field (name "MFG") "Toshiba Semiconductor and Storage") (field (name "MFG P/N") "TCR2LN33,LF"))
      (libsource (lib "AltiumReleaseLibDB") (part "REG_LIN_TCR2LN33"))
    )
    (comp (ref "U5")
      (value "MCU_MIMXRT1176CVM8A")
      (footprint "BGA289C80P17X17_1400X14000X152")
      (description "IC, PROCESSOR, MIMXRT1176CV, ARM CORTEX-M4/M7, 2MB RAM, SDRAM, WLAN, BGA-289")
      (fields (field (name "MFG") "NXP Semiconductors") (field (name "MFG P/N") "MIMXRT1176CVM8A"))
      (libsource (lib "AltiumReleaseLibDB") (part "MCU_MIMXRT1176CVM8A"))
    )
    (comp (ref "X1")
      (value "XTAL_MURATA_XRCGB24M000F1H01R0")
      (footprint "XTAL_MURATA_XRCGB24M000F1H01R0")
      (description "XTAL, 24MHz, +/-10PPM STAB, +/-10PPM, 8pF, 80 OHM, SMD-4")
      (fields
        (field (name "MFG") "XRCGB24M000F1H01R0")
        (field (name "MFG P/N") "Murata Electronics")
        (field (name "FREQUENCY") "24 MHz")
      )
      (libsource (lib "AltiumReleaseLibDB") (part "XTAL_MURATA_XRCGB24M000F1H01R0"))
    )
    (comp (ref "X2")
      (value "__template_xtal")
      (footprint "XTAL_EPSON_ADUCM355BCCZ")
      (description "XTAL, 32.7680KHz, +/-20PPM, 7pF, 70 KOHM, SMD-2\nXTAL, 32.7680KHz, +/-20PPM, 7pF, 70 KOHM, SMD-2\"")
      (fields (field (name "MFG") "FC-135 32.7680KA-AG3") (field (name "MFG P/N") "EPSON"))
      (libsource (lib "AltiumReleaseLibDB") (part "__template_xtal"))
    )
  )
  (nets
    (net (code "1") (name "/BRD_STAT_LED") (class "Default")
      (node (ref "U5") (pin "L9") (pinfunction "GPIO_SNVS_02_L9") (pintype "bidirectional"))
    )
    (net (code "2") (name "/DAC_OUT") (class "Default")
      (node (ref "D31") (pin "K") (pinfunction "K_K") (pintype "passive"))
      (node (ref "U5") (pin "H16") (pinfunction "DAC_OUT_H16") (pintype "passive"))
    )
    (net (code "3") (name "/DA_GPIO0_WDOG_KICK") (class "Default")
      (node (ref "U5") (pin "P10") (pinfunction "GPIO_SNVS_01_P10") (pintype "bidirectional"))
    )
    (net (code "4") (name "/DCDC_PSWITCH") (class "Default")
      (node (ref "C286") (pin "1") (pintype "passive"))
      (node (ref "R396") (pin "2") (pintype "passive"))
      (node (ref "U5") (pin "P3") (pinfunction "DCDC_PSWITCH_P3") (pintype "passive"))
    )
    (net (code "5") (name "/GPIO_SNVS_04") (class "Default")
      (node (ref "U5") (pin "N10") (pinfunction "GPIO_SNVS_04_N10") (pintype "bidirectional"))
    )
    (net (code "6") (name "/GPIO_SNVS_06") (class "Default")
      (node (ref "U5") (pin "M9") (pinfunction "GPIO_SNVS_06_M9") (pintype "bidirectional"))
    )
    (net (code "7") (name "/GPIO_SNVS_07") (class "Default")
      (node (ref "U5") (pin "R9") (pinfunction "GPIO_SNVS_07_R9") (pintype "bidirectional"))
    )
    (net (code "8") (name "/GPIO_SNVS_08") (class "Default")
      (node (ref "U5") (pin "N9") (pinfunction "GPIO_SNVS_08_N9") (pintype "bidirectional"))
    )
    (net (code "9") (name "/INT_AFE0") (class "Default")
      (node (ref "U5") (pin "P9") (pinfunction "GPIO_SNVS_05_P9") (pintype "bidirectional"))
    )
    (net (code "10") (name "/ONOFF") (class "Default")
      (node (ref "U5") (pin "U10") (pinfunction "ONOFF_U10") (pintype "input"))
    )
    (net (code "11") (name "/PMIC_ON_REQ") (class "Default")
      (node (ref "R1821") (pin "1") (pintype "passive"))
      (node (ref "TP13") (pin "1") (pintype "passive"))
      (node (ref "U5") (pin "U9") (pinfunction "PMIC_ON_REQ_U9") (pintype "passive"))
    )
    (net (code "12") (name "/PMIC_STBY_REQ") (class "Default")
      (node (ref "TP12") (pin "1") (pintype "passive"))
      (node (ref "U5") (pin "T9") (pinfunction "PMIC_STBY_REQ_T9") (pintype "passive"))
    )
    (net (code "13") (name "/POR_B") (class "Default")
      (node (ref "C115") (pin "1") (pintype "passive"))
      (node (ref "R215") (pin "1") (pintype "passive"))
      (node (ref "U5") (pin "T10") (pinfunction "~{POR}_T10") (pintype "input"))
    )
    (net (code "14") (name "/RTC_XTALI") (class "Default")
      (node (ref "C110") (pin "1") (pintype "passive"))
      (node (ref "U5") (pin "T13") (pinfunction "RTC_XTALI_T13") (pintype "input"))
      (node (ref "X2") (pin "1") (pinfunction "1_1") (pintype "passive"))
    )
    (net (code "15") (name "/RTC_XTALO") (class "Default")
      (node (ref "C109") (pin "1") (pintype "passive"))
      (node (ref "U5") (pin "U13") (pinfunction "RTC_XTALO_U13") (pintype "output"))
      (node (ref "X2") (pin "2") (pinfunction "2_2") (pintype "passive"))
    )
    (net (code "16") (name "/RT_CLK1_N") (class "Default")
      (node (ref "TP22") (pin "1") (pintype "passive"))
      (node (ref "U5") (pin "T15") (pinfunction "CLK1_N_T15") (pintype "passive"))
    )
    (net (code "17") (name "/RT_CLK1_P") (class "Default")
      (node (ref "TP23") (pin "1") (pintype "passive"))
      (node (ref "U5") (pin "U15") (pinfunction "CLK1_P_U15") (pintype "passive"))
    )
    (net (code "18") (name "/RT_DCDC_L_1") (class "Default")
      (node (ref "L15") (pin "1") (pintype "passive"))
      (node (ref "U5") (pin "T3") (pinfunction "DCDC_LP_1_T3") (pintype "passive"))
      (node (ref "U5") (pin "U3") (pinfunction "DCDC_LP_2_U3") (pintype "passive"))
    )
    (net (code "19") (name "/RT_DCDC_L_2") (class "Default")
      (node (ref "L15") (pin "2") (pintype "passive"))
      (node (ref "U5") (pin "T4") (pinfunction "DCDC_LN_1_T4") (pintype "passive"))
      (node (ref "U5") (pin "U4") (pinfunction "DCDC_LN_2_U4") (pintype "passive"))
    )
    (net (code "20") (name "/RT_DCDC_MODE") (class "Default")
      (node (ref "C287") (pin "1") (pintype "passive"))
      (node (ref "R397") (pin "2") (pintype "passive"))
      (node (ref "R398") (pin "2") (pintype "passive"))
      (node (ref "U5") (pin "N4") (pinfunction "DCDC_MODE_N4") (pintype "passive"))
    )
    (net (code "21") (name "/RT_TEST_MODE") (class "Default")
      (node (ref "R14") (pin "1") (pintype "passive"))
      (node (ref "U5") (pin "T11") (pinfunction "TEST_MODE_T11") (pintype "input"))
    )
    (net (code "22") (name "/RT_XTALI") (class "Default")
      (node (ref "C316") (pin "2") (pintype "passive"))
      (node (ref "R189") (pin "2") (pintype "passive"))
      (node (ref "U5") (pin "U16") (pinfunction "XTALI_U16") (pintype "input"))
      (node (ref "X1") (pin "1") (pinfunction "1_1") (pintype "passive"))
    )
    (net (code "23") (name "/RT_XTALO") (class "Default")
      (node (ref "C317") (pin "1") (pintype "passive"))
      (node (ref "R189") (pin "1") (pintype "passive"))
      (node (ref "U5") (pin "T16") (pinfunction "XTALO_T16") (pintype "output"))
      (node (ref "X1") (pin "3") (pinfunction "3_3") (pintype "passive"))
    )
    (net (code "24") (name "/USER_BUTTON") (class "Default")
      (node (ref "U5") (pin "R10") (pinfunction "GPIO_SNVS_00_R10") (pintype "bidirectional"))
    )
    (net (code "25") (name "/USER_LED") (class "Default")
      (node (ref "U5") (pin "M10") (pinfunction "GPIO_SNVS_03_M10") (pintype "bidirectional"))
    )
    (net (code "26") (name "/VDDA_ADC_3P3") (class "Default")
      (node (ref "C245") (pin "1") (pintype "passive"))
      (node (ref "C257") (pin "1") (pintype "passive"))
      (node (ref "FB1") (pin "1") (pinfunction "1_1") (pintype "passive"))
      (node (ref "U5") (pin "J13") (pinfunction "VDDA_ADC_3P3_J13") (pintype "power_in"))
    )
    (net (code "27") (name "/VDD_SNVS") (class "Default")
      (node (ref "C302") (pin "1") (pintype "passive"))
      (node (ref "R419") (pin "2") (pintype "passive"))
      (node (ref "TP11") (pin "1") (pintype "passive"))
      (node (ref "U5") (pin "U12") (pinfunction "VDD_SNVS_IN_U12") (pintype "power_in"))
    )
    (net (code "28") (name "/VSYS_SNVS_D") (class "Default")
      (node (ref "C21") (pin "1") (pintype "passive"))
      (node (ref "D2") (pin "A") (pinfunction "A_A") (pintype "passive"))
      (node (ref "U2") (pin "1") (pinfunction "VOUT_1") (pintype "power_in"))
    )
    (net (code "29") (name "/WAKEUP") (class "Default")
      (node (ref "TP9") (pin "1") (pintype "passive"))
      (node (ref "U5") (pin "T8") (pinfunction "WAKEUP_T8") (pintype "passive"))
    )
    (net (code "30") (name "/WIFI_POWER_EN") (class "Default")
      (node (ref "U5") (pin "R11") (pinfunction "GPIO_SNVS_09_R11") (pintype "bidirectional"))
    )
    (net (code "31") (name "ADC_1V8_IN") (class "Default")
      (node (ref "C117") (pin "1") (pintype "passive"))
      (node (ref "C136") (pin "1") (pintype "passive"))
      (node (ref "C347") (pin "1") (pintype "passive"))
      (node (ref "C348") (pin "1") (pintype "passive"))
      (node (ref "FB2") (pin "2") (pinfunction "2_2") (pintype "passive"))
      (node (ref "U5") (pin "G16") (pinfunction "ADC_VREFH_G16") (pintype "passive"))
      (node (ref "U5") (pin "K15") (pinfunction "VDDA_ADC_1P8_K15") (pintype "power_in"))
      (node (ref "U5") (pin "M11") (pinfunction "VDDA_1P8_IN_M11") (pintype "power_in"))
    )
    (net (code "32") (name "DCDC_1V8_OUT") (class "Default")
      (node (ref "C279") (pin "1") (pintype "passive"))
      (node (ref "FB2") (pin "1") (pinfunction "1_1") (pintype "passive"))
      (node (ref "R416") (pin "2") (pintype "passive"))
      (node (ref "U5") (pin "M6") (pinfunction "DCDC_ANA_SENSE_M6") (pintype "passive"))
    )
    (net (code "33") (name "DCDC_1V8_OUT_SENSE") (class "Default")
      (node (ref "C118") (pin "1") (pintype "passive"))
      (node (ref "C124") (pin "1") (pintype "passive"))
      (node (ref "C138") (pin "1") (pintype "passive"))
      (node (ref "C280") (pin "1") (pintype "passive"))
      (node (ref "R416") (pin "1") (pintype "passive"))
      (node (ref "U5") (pin "M7") (pinfunction "DCDC_ANA_1_M7") (pintype "passive"))
      (node (ref "U5") (pin "M8") (pinfunction "DCDC_ANA_2_M8") (pintype "passive"))
    )
    (net (code "34") (name "GND") (class "Default")
      (node (ref "C102") (pin "2") (pintype "passive"))
      (node (ref "C107") (pin "2") (pintype "passive"))
      (node (ref "C109") (pin "2") (pintype "passive"))
      (node (ref "C110") (pin "2") (pintype "passive"))
      (node (ref "C115") (pin "2") (pintype "passive"))
      (node (ref "C117") (pin "2") (pintype "passive"))
      (node (ref "C118") (pin "2") (pintype "passive"))
      (node (ref "C124") (pin "2") (pintype "passive"))
      (node (ref "C136") (pin "2") (pintype "passive"))
      (node (ref "C138") (pin "2") (pintype "passive"))
      (node (ref "C18") (pin "2") (pintype "passive"))
      (node (ref "C21") (pin "2") (pintype "passive"))
      (node (ref "C245") (pin "2") (pintype "passive"))
      (node (ref "C257") (pin "2") (pintype "passive"))
      (node (ref "C260") (pin "2") (pintype "passive"))
      (node (ref "C261") (pin "2") (pintype "passive"))
      (node (ref "C264") (pin "2") (pintype "passive"))
      (node (ref "C266") (pin "2") (pintype "passive"))
      (node (ref "C269") (pin "2") (pintype "passive"))
      (node (ref "C273") (pin "2") (pintype "passive"))
      (node (ref "C276") (pin "2") (pintype "passive"))
      (node (ref "C277") (pin "2") (pintype "passive"))
      (node (ref "C279") (pin "2") (pintype "passive"))
      (node (ref "C280") (pin "2") (pintype "passive"))
      (node (ref "C286") (pin "2") (pintype "passive"))
      (node (ref "C287") (pin "2") (pintype "passive"))
      (node (ref "C290") (pin "2") (pintype "passive"))
      (node (ref "C293") (pin "2") (pintype "passive"))
      (node (ref "C294") (pin "2") (pintype "passive"))
      (node (ref "C296") (pin "2") (pintype "passive"))
      (node (ref "C300") (pin "2") (pintype "passive"))
      (node (ref "C302") (pin "2") (pintype "passive"))
      (node (ref "C305") (pin "2") (pintype "passive"))
      (node (ref "C316") (pin "1") (pintype "passive"))
      (node (ref "C317") (pin "2") (pintype "passive"))
      (node (ref "C347") (pin "2") (pintype "passive"))
      (node (ref "C348") (pin "2") (pintype "passive"))
      (node (ref "C57") (pin "2") (pintype "passive"))
      (node (ref "C61") (pin "2") (pintype "passive"))
      (node (ref "C62") (pin "2") (pintype "passive"))
      (node (ref "C63") (pin "2") (pintype "passive"))
      (node (ref "C67") (pin "2") (pintype "passive"))
      (node (ref "C74") (pin "2") (pintype "passive"))
      (node (ref "D31") (pin "A") (pinfunction "A_A") (pintype "passive"))
      (node (ref "R14") (pin "2") (pintype "passive"))
      (node (ref "R398") (pin "1") (pintype "passive"))
      (node (ref "U2") (pin "2") (pinfunction "GND_2") (pintype "power_in"))
      (node (ref "U2") (pin "5") (pinfunction "TP-GND_5") (pintype "power_in"))
      (node (ref "U5") (pin "A1") (pinfunction "VSS_1_A1") (pintype "power_in"))
      (node (ref "U5") (pin "A17") (pinfunction "VSS_2_A17") (pintype "power_in"))
      (node (ref "U5") (pin "B7") (pinfunction "VSS_3_B7") (pintype "power_in"))
      (node (ref "U5") (pin "C10") (pinfunction "VSS_5_C10") (pintype "power_in"))
      (node (ref "U5") (pin "C12") (pinfunction "VSS_6_C12") (pintype "power_in"))
      (node (ref "U5") (pin "C14") (pinfunction "VSS_7_C14") (pintype "power_in"))
      (node (ref "U5") (pin "C8") (pinfunction "VSS_4_C8") (pintype "power_in"))
      (node (ref "U5") (pin "D4") (pinfunction "VSS_8_D4") (pintype "power_in"))
      (node (ref "U5") (pin "F11") (pinfunction "VSS_9_F11") (pintype "power_in"))
      (node (ref "U5") (pin "F12") (pinfunction "VSS_10_F12") (pintype "power_in"))
      (node (ref "U5") (pin "F13") (pinfunction "VSS_11_F13") (pintype "power_in"))
      (node (ref "U5") (pin "G10") (pinfunction "VSS_16_G10") (pintype "power_in"))
      (node (ref "U5") (pin "G11") (pinfunction "VSS_17_G11") (pintype "power_in"))
      (node (ref "U5") (pin "G15") (pinfunction "VSS_18_G15") (pintype "power_in"))
      (node (ref "U5") (pin "G3") (pinfunction "VSS_12_G3") (pintype "power_in"))
      (node (ref "U5") (pin "G7") (pinfunction "VSS_13_G7") (pintype "power_in"))
      (node (ref "U5") (pin "G8") (pinfunction "VSS_14_G8") (pintype "power_in"))
      (node (ref "U5") (pin "G9") (pinfunction "VSS_15_G9") (pintype "power_in"))
      (node (ref "U5") (pin "H11") (pinfunction "VSS_20_H11") (pintype "power_in"))
      (node (ref "U5") (pin "H7") (pinfunction "VSS_19_H7") (pintype "power_in"))
      (node (ref "U5") (pin "J11") (pinfunction "VSS_22_J11") (pintype "power_in"))
      (node (ref "U5") (pin "J7") (pinfunction "VSS_21_J7") (pintype "power_in"))
      (node (ref "U5") (pin "K11") (pinfunction "VSS_23_K11") (pintype "power_in"))
      (node (ref "U5") (pin "K6") (pinfunction "DCDC_GND_1_K6") (pintype "power_in"))
      (node (ref "U5") (pin "K7") (pinfunction "DCDC_GND_2_K7") (pintype "power_in"))
      (node (ref "U5") (pin "L10") (pinfunction "VSS_25_L10") (pintype "power_in"))
      (node (ref "U5") (pin "L11") (pinfunction "VSS_26_L11") (pintype "power_in"))
      (node (ref "U5") (pin "L15") (pinfunction "VSS_27_L15") (pintype "power_in"))
      (node (ref "U5") (pin "L3") (pinfunction "VSS_24_L3") (pintype "power_in"))
      (node (ref "U5") (pin "L6") (pinfunction "DCDC_GND_3_L6") (pintype "power_in"))
      (node (ref "U5") (pin "P14") (pinfunction "VSS_29_P14") (pintype "power_in"))
      (node (ref "U5") (pin "P4") (pinfunction "VSS_28_P4") (pintype "power_in"))
      (node (ref "U5") (pin "R4") (pinfunction "VSS_34_R4") (pintype "power_in"))
      (node (ref "U5") (pin "R7") (pinfunction "VSS_30_R7") (pintype "power_in"))
      (node (ref "U5") (pin "T12") (pinfunction "VSS_31_T12") (pintype "power_in"))
      (node (ref "U5") (pin "U1") (pinfunction "VSS_32_U1") (pintype "power_in"))
      (node (ref "U5") (pin "U17") (pinfunction "VSS_33_U17") (pintype "power_in"))
      (node (ref "X1") (pin "2") (pinfunction "GND_2") (pintype "power_in"))
      (node (ref "X1") (pin "4") (pinfunction "GND_4") (pintype "power_in"))
    )
    (net (code "35") (name "MCU_DCDC_IN") (class "Default")
      (node (ref "C102") (pin "1") (pintype "passive"))
      (node (ref "C277") (pin "1") (pintype "passive"))
      (node (ref "C294") (pin "1") (pintype "passive"))
      (node (ref "R194") (pin "2") (pintype "passive"))
      (node (ref "R396") (pin "1") (pintype "passive"))
      (node (ref "R397") (pin "1") (pintype "passive"))
      (node (ref "TP17") (pin "1") (pintype "passive"))
      (node (ref "U5") (pin "L5") (pinfunction "DCDC_IN_Q_L5") (pintype "passive"))
      (node (ref "U5") (pin "M5") (pinfunction "DCDC_IN_1_M5") (pintype "passive"))
      (node (ref "U5") (pin "N5") (pinfunction "DCDC_IN_2_N5") (pintype "passive"))
    )
    (net (code "36") (name "Net-(U5C-DCDC_DIG_1)") (class "Default")
      (node (ref "C269") (pin "1") (pintype "passive"))
      (node (ref "C57") (pin "1") (pintype "passive"))
      (node (ref "C63") (pin "1") (pintype "passive"))
      (node (ref "C74") (pin "1") (pintype "passive"))
      (node (ref "R117") (pin "1") (pintype "passive"))
      (node (ref "U5") (pin "K8") (pinfunction "DCDC_DIG_1_K8") (pintype "passive"))
      (node (ref "U5") (pin "K9") (pinfunction "DCDC_DIG_2_K9") (pintype "passive"))
      (node (ref "U5") (pin "L8") (pinfunction "DCDC_DIG_3_L8") (pintype "passive"))
    )
    (net (code "37") (name "VDDA_1P0") (class "Default")
      (node (ref "C276") (pin "1") (pintype "passive"))
      (node (ref "U5") (pin "N11") (pinfunction "VDDA_1P0_N11") (pintype "power_in"))
    )
    (net (code "38") (name "VDD_3V3") (class "Default")
      (node (ref "FB1") (pin "2") (pinfunction "2_2") (pintype "passive"))
      (node (ref "R194") (pin "1") (pintype "passive"))
      (node (ref "R415") (pin "1") (pintype "passive"))
      (node (ref "TP14") (pin "1") (pintype "passive"))
      (node (ref "TP16") (pin "1") (pintype "passive"))
    )
    (net (code "39") (name "VDD_COIN_3V") (class "Default")
      (node (ref "D3") (pin "A") (pinfunction "A_A") (pintype "passive"))
    )
    (net (code "40") (name "VDD_LPSR_ANA") (class "Default")
      (node (ref "C290") (pin "1") (pintype "passive"))
      (node (ref "U5") (pin "P12") (pinfunction "VDD_LPSR_ANA_P12") (pintype "power_in"))
    )
    (net (code "41") (name "VDD_LPSR_DIG") (class "Default")
      (node (ref "C296") (pin "1") (pintype "passive"))
      (node (ref "U5") (pin "P11") (pinfunction "VDD_LPSR_DIG_P11") (pintype "power_in"))
    )
    (net (code "42") (name "VDD_LPSR_IN") (class "Default")
      (node (ref "C300") (pin "1") (pintype "passive"))
      (node (ref "R415") (pin "2") (pintype "passive"))
      (node (ref "TP15") (pin "1") (pintype "passive"))
      (node (ref "U5") (pin "R12") (pinfunction "VDD_LPSR_IN_R12") (pintype "power_in"))
    )
    (net (code "43") (name "VDD_SNVS_3V3") (class "Default")
      (node (ref "D2") (pin "K") (pinfunction "K_K") (pintype "passive"))
      (node (ref "D3") (pin "K") (pinfunction "K_K") (pintype "passive"))
      (node (ref "R419") (pin "1") (pintype "passive"))
      (node (ref "TP10") (pin "1") (pintype "passive"))
    )
    (net (code "44") (name "VDD_SNVS_ANA") (class "Default")
      (node (ref "C293") (pin "1") (pintype "passive"))
      (node (ref "C305") (pin "1") (pintype "passive"))
      (node (ref "R1821") (pin "2") (pintype "passive"))
      (node (ref "R215") (pin "2") (pintype "passive"))
      (node (ref "U5") (pin "U11") (pinfunction "NVCC_SNVS_U11") (pintype "passive"))
      (node (ref "U5") (pin "U14") (pinfunction "VDD_SNVS_ANA_U14") (pintype "power_in"))
    )
    (net (code "45") (name "VDD_SNVS_DIG") (class "Default")
      (node (ref "C107") (pin "1") (pintype "passive"))
      (node (ref "U5") (pin "T14") (pinfunction "VDD_SNVS_DIG_T14") (pintype "power_in"))
    )
    (net (code "46") (name "VDD_SOC_IN") (class "Default")
      (node (ref "C260") (pin "1") (pintype "passive"))
      (node (ref "C261") (pin "1") (pintype "passive"))
      (node (ref "C264") (pin "1") (pintype "passive"))
      (node (ref "C266") (pin "1") (pintype "passive"))
      (node (ref "C273") (pin "1") (pintype "passive"))
      (node (ref "C61") (pin "1") (pintype "passive"))
      (node (ref "C62") (pin "1") (pintype "passive"))
      (node (ref "C67") (pin "1") (pintype "passive"))
      (node (ref "R117") (pin "2") (pintype "passive"))
      (node (ref "U5") (pin "H10") (pinfunction "VDD_SOC_IN_3_H10") (pintype "passive"))
      (node (ref "U5") (pin "H8") (pinfunction "VDD_SOC_IN_1_H8") (pintype "passive"))
      (node (ref "U5") (pin "H9") (pinfunction "VDD_SOC_IN_2_H9") (pintype "passive"))
      (node (ref "U5") (pin "J10") (pinfunction "VDD_SOC_IN_6_J10") (pintype "passive"))
      (node (ref "U5") (pin "J8") (pinfunction "VDD_SOC_IN_4_J8") (pintype "passive"))
      (node (ref "U5") (pin "J9") (pinfunction "VDD_SOC_IN_5_J9") (pintype "passive"))
      (node (ref "U5") (pin "K10") (pinfunction "VDD_SOC_IN_7_K10") (pintype "passive"))
      (node (ref "U5") (pin "L7") (pinfunction "DCDC_DIG_SENSE_L7") (pintype "passive"))
    )
    (net (code "47") (name "VSYS") (class "Default")
      (node (ref "C18") (pin "1") (pintype "passive"))
      (node (ref "U2") (pin "3") (pinfunction "CONTROL_3") (pintype "passive"))
      (node (ref "U2") (pin "4") (pinfunction "VIN_4") (pintype "power_in"))
    )
  )
)
